# ism-boardlet.net
KiCad netlist of a schematic drawn in EAGLE
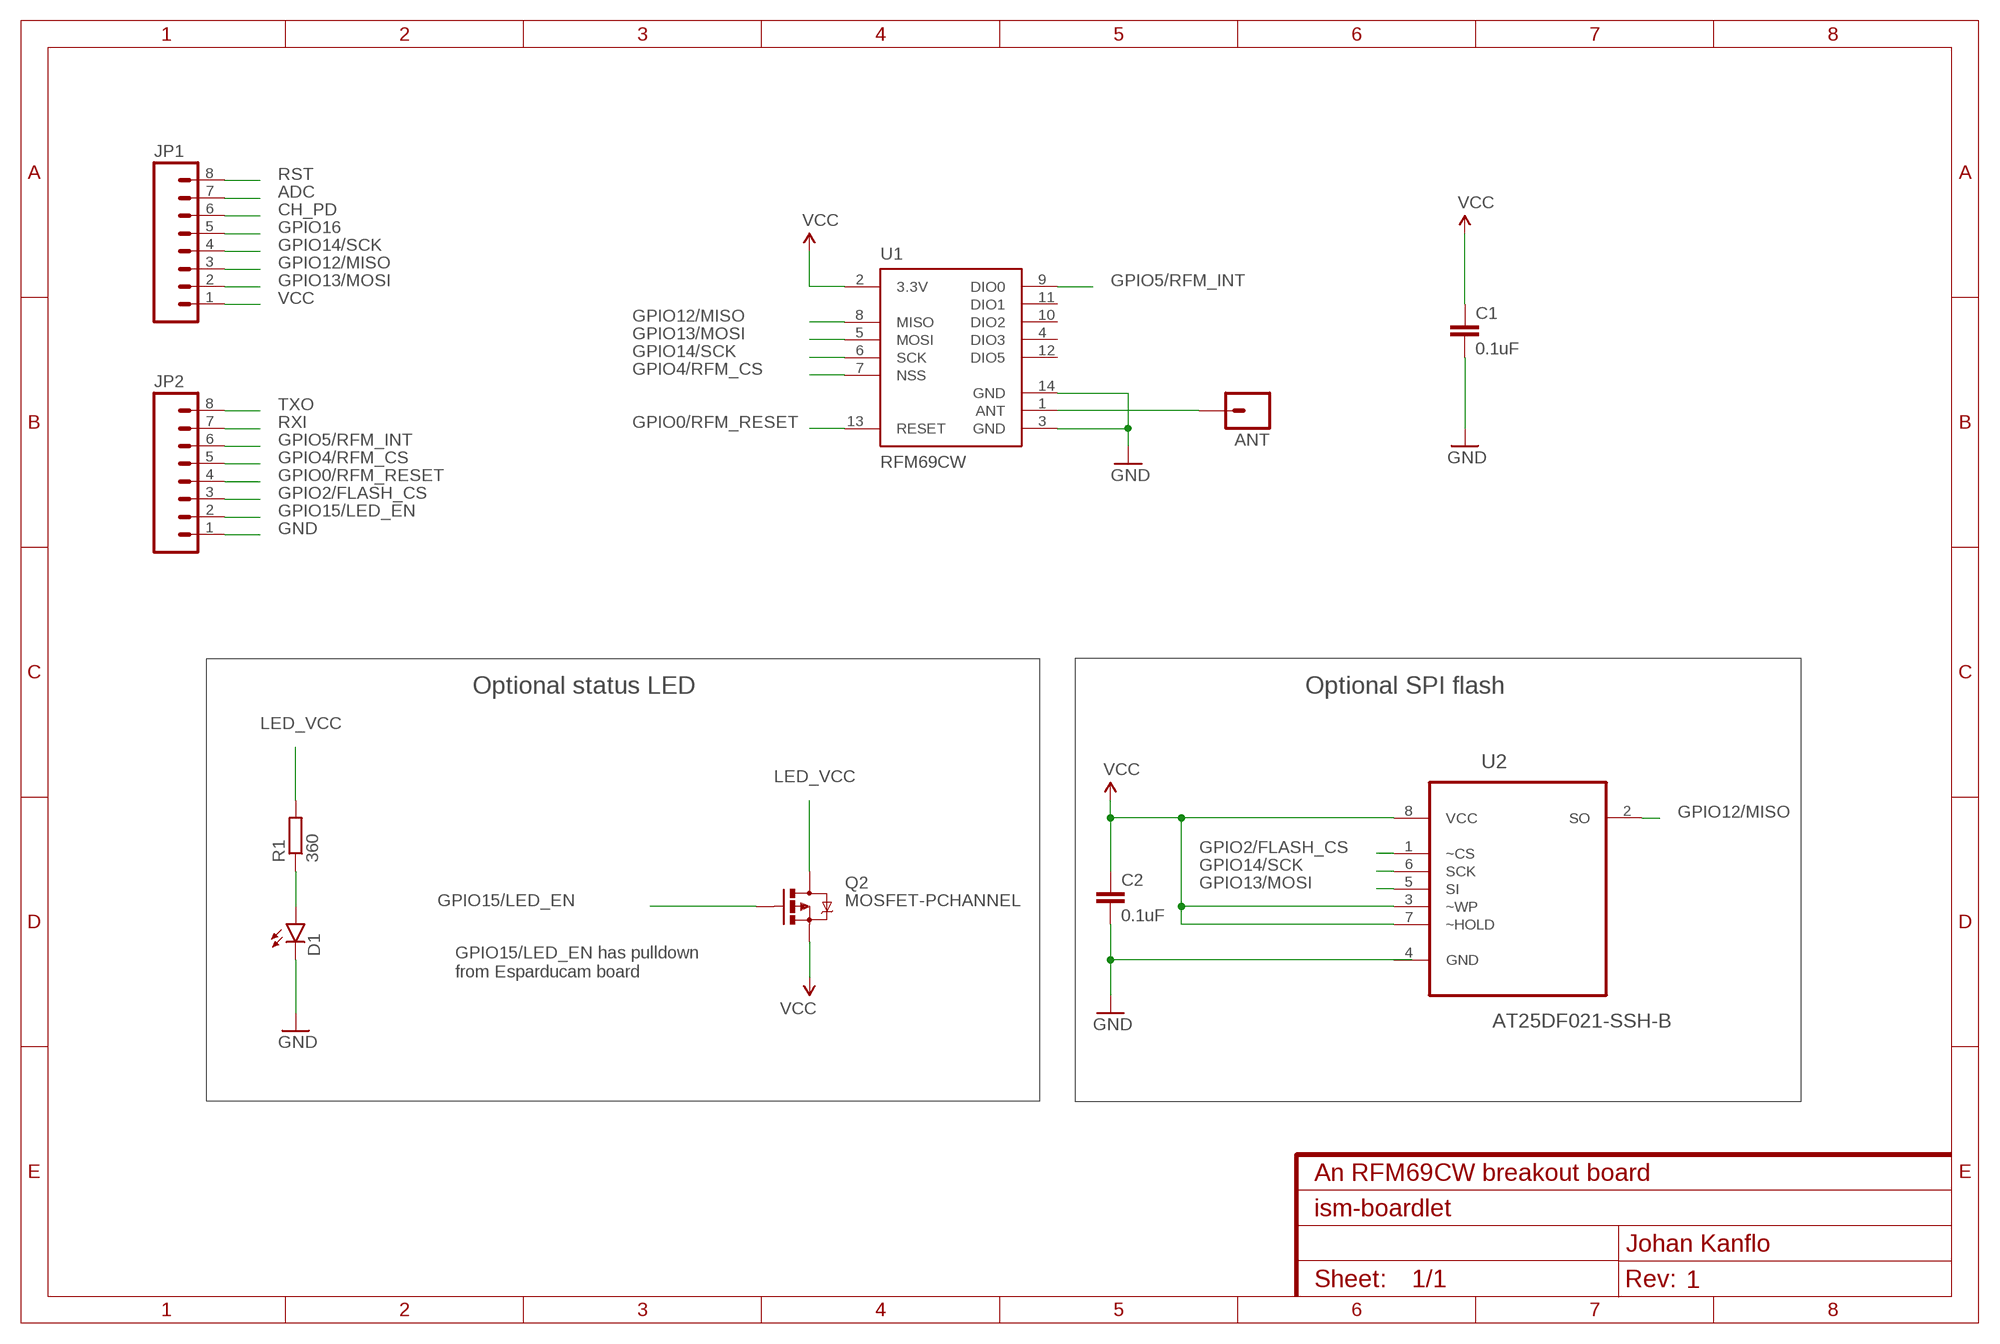
[diagram p0: schematic, sheet 1]

(export (version "E")
  (design (tool "Eeschema 10.0.6"))
  (components
    (comp (ref "ANT")
      (value "M01PTH")
      (footprint "eagle-import:1X01")
      (libsource (lib "eagle-import") (part "M01PTH"))
    )
    (comp (ref "C1")
      (value "0.1uF")
      (footprint "eagle-import:0603-CAP")
      (libsource (lib "eagle-import") (part "CAP0603-CAP"))
    )
    (comp (ref "C2")
      (value "0.1uF")
      (footprint "eagle-import:0603-CAP")
      (libsource (lib "eagle-import") (part "CAP0603-CAP"))
    )
    (comp (ref "D1")
      (value "LED0603")
      (footprint "eagle-import:LED-0603")
      (libsource (lib "eagle-import") (part "LED0603"))
    )
    (comp (ref "JP1")
      (value "M08")
      (footprint "eagle-import:1X08_ROUND")
      (libsource (lib "eagle-import") (part "M08"))
    )
    (comp (ref "JP2")
      (value "M08")
      (footprint "eagle-import:1X08_ROUND")
      (libsource (lib "eagle-import") (part "M08"))
    )
    (comp (ref "Q2")
      (value "MOSFET-PCHANNEL")
      (footprint "eagle-import:SOT23-3")
      (libsource (lib "eagle-import") (part "MOSFET-PCHANNEL"))
    )
    (comp (ref "R1")
      (value "360")
      (footprint "eagle-import:R0603")
      (libsource (lib "eagle-import") (part "R-EU_R0603"))
    )
    (comp (ref "U1")
      (value "RFM69CW")
      (footprint "eagle-import:RFM69CW-XXXS2")
      (libsource (lib "eagle-import") (part "RFM69CW"))
    )
    (comp (ref "U2")
      (value "AT25DF021-SSH-B")
      (footprint "eagle-import:SOIC127P600X175-8N")
      (libsource (lib "eagle-import") (part "AT25DF021-SSH-B"))
    )
  )
  (nets
    (net (code "1") (name "/ADC") (class "Default")
      (node (ref "JP1") (pin "7") (pinfunction "7_7") (pintype "passive"))
    )
    (net (code "2") (name "/CH_PD") (class "Default")
      (node (ref "JP1") (pin "6") (pinfunction "6_6") (pintype "passive"))
    )
    (net (code "3") (name "/GPIO0{slash}RFM_RESET") (class "Default")
      (node (ref "JP2") (pin "4") (pinfunction "4_4") (pintype "passive"))
      (node (ref "U1") (pin "13") (pinfunction "RESET_13") (pintype "input"))
    )
    (net (code "4") (name "/GPIO2{slash}FLASH_CS") (class "Default")
      (node (ref "JP2") (pin "3") (pinfunction "3_3") (pintype "passive"))
      (node (ref "U2") (pin "1") (pinfunction "~{CS}_1") (pintype "input"))
    )
    (net (code "5") (name "/GPIO4{slash}RFM_CS") (class "Default")
      (node (ref "JP2") (pin "5") (pinfunction "5_5") (pintype "passive"))
      (node (ref "U1") (pin "7") (pinfunction "NSS_7") (pintype "input"))
    )
    (net (code "6") (name "/GPIO5{slash}RFM_INT") (class "Default")
      (node (ref "JP2") (pin "6") (pinfunction "6_6") (pintype "passive"))
      (node (ref "U1") (pin "9") (pinfunction "DIO0_9") (pintype "bidirectional"))
    )
    (net (code "7") (name "/GPIO12{slash}MISO") (class "Default")
      (node (ref "JP1") (pin "3") (pinfunction "3_3") (pintype "passive"))
      (node (ref "U1") (pin "8") (pinfunction "MISO_8") (pintype "bidirectional"))
      (node (ref "U2") (pin "2") (pinfunction "SO_2") (pintype "output"))
    )
    (net (code "8") (name "/GPIO13{slash}MOSI") (class "Default")
      (node (ref "JP1") (pin "2") (pinfunction "2_2") (pintype "passive"))
      (node (ref "U1") (pin "5") (pinfunction "MOSI_5") (pintype "input"))
      (node (ref "U2") (pin "5") (pinfunction "SI_5") (pintype "input"))
    )
    (net (code "9") (name "/GPIO14{slash}SCK") (class "Default")
      (node (ref "JP1") (pin "4") (pinfunction "4_4") (pintype "passive"))
      (node (ref "U1") (pin "6") (pinfunction "SCK_6") (pintype "input"))
      (node (ref "U2") (pin "6") (pinfunction "SCK_6") (pintype "input"))
    )
    (net (code "10") (name "/GPIO15{slash}LED_EN") (class "Default")
      (node (ref "JP2") (pin "2") (pinfunction "2_2") (pintype "passive"))
      (node (ref "Q2") (pin "1") (pinfunction "G_1") (pintype "passive"))
    )
    (net (code "11") (name "/GPIO16") (class "Default")
      (node (ref "JP1") (pin "5") (pinfunction "5_5") (pintype "passive"))
    )
    (net (code "12") (name "/LED_VCC") (class "Default")
      (node (ref "Q2") (pin "3") (pinfunction "D_3") (pintype "passive"))
      (node (ref "R1") (pin "2") (pinfunction "2_2") (pintype "passive"))
    )
    (net (code "13") (name "/RST") (class "Default")
      (node (ref "JP1") (pin "8") (pinfunction "8_8") (pintype "passive"))
    )
    (net (code "14") (name "/RXI") (class "Default")
      (node (ref "JP2") (pin "7") (pinfunction "7_7") (pintype "passive"))
    )
    (net (code "15") (name "/TXO") (class "Default")
      (node (ref "JP2") (pin "8") (pinfunction "8_8") (pintype "passive"))
    )
    (net (code "16") (name "GND") (class "Default")
      (node (ref "C1") (pin "2") (pinfunction "2_2") (pintype "passive"))
      (node (ref "C2") (pin "2") (pinfunction "2_2") (pintype "passive"))
      (node (ref "D1") (pin "C") (pinfunction "C_C") (pintype "passive"))
      (node (ref "JP2") (pin "1") (pinfunction "1_1") (pintype "passive"))
      (node (ref "U1") (pin "14") (pinfunction "GND_14") (pintype "power_in"))
      (node (ref "U1") (pin "3") (pinfunction "GND_3") (pintype "power_in"))
    )
    (net (code "17") (name "Net-(D1-PadA)") (class "Default")
      (node (ref "D1") (pin "A") (pinfunction "A_A") (pintype "passive"))
      (node (ref "R1") (pin "1") (pinfunction "1_1") (pintype "passive"))
    )
    (net (code "18") (name "Net-(U1-ANT)") (class "Default")
      (node (ref "ANT") (pin "1") (pinfunction "1_1") (pintype "passive"))
      (node (ref "U1") (pin "1") (pinfunction "ANT_1") (pintype "passive"))
    )
    (net (code "19") (name "VCC") (class "Default")
      (node (ref "C1") (pin "1") (pinfunction "1_1") (pintype "passive"))
      (node (ref "C2") (pin "1") (pinfunction "1_1") (pintype "passive"))
      (node (ref "JP1") (pin "1") (pinfunction "1_1") (pintype "passive"))
      (node (ref "Q2") (pin "2") (pinfunction "S_2") (pintype "passive"))
      (node (ref "U1") (pin "2") (pinfunction "3.3V_2") (pintype "power_in"))
      (node (ref "U2") (pin "3") (pinfunction "~{WP}_3") (pintype "input"))
      (node (ref "U2") (pin "7") (pinfunction "~{HOLD}_7") (pintype "input"))
      (node (ref "U2") (pin "8") (pinfunction "VCC_8") (pintype "power_in"))
    )
    (net (code "20") (name "unconnected-(U1-DIO1-Pad11)") (class "Default")
      (node (ref "U1") (pin "11") (pinfunction "DIO1_11") (pintype "bidirectional"))
    )
    (net (code "21") (name "unconnected-(U1-DIO2-Pad10)") (class "Default")
      (node (ref "U1") (pin "10") (pinfunction "DIO2_10") (pintype "bidirectional"))
    )
    (net (code "22") (name "unconnected-(U1-DIO3-Pad4)") (class "Default")
      (node (ref "U1") (pin "4") (pinfunction "DIO3_4") (pintype "bidirectional"))
    )
    (net (code "23") (name "unconnected-(U1-DIO5-Pad12)") (class "Default")
      (node (ref "U1") (pin "12") (pinfunction "DIO5_12") (pintype "bidirectional"))
    )
    (net (code "24") (name "unconnected-(U2-GND-Pad4)") (class "Default")
      (node (ref "U2") (pin "4") (pinfunction "GND_4") (pintype "passive"))
    )
  )
)
